# USB.net
KiCad netlist of a schematic drawn in Altium Designer
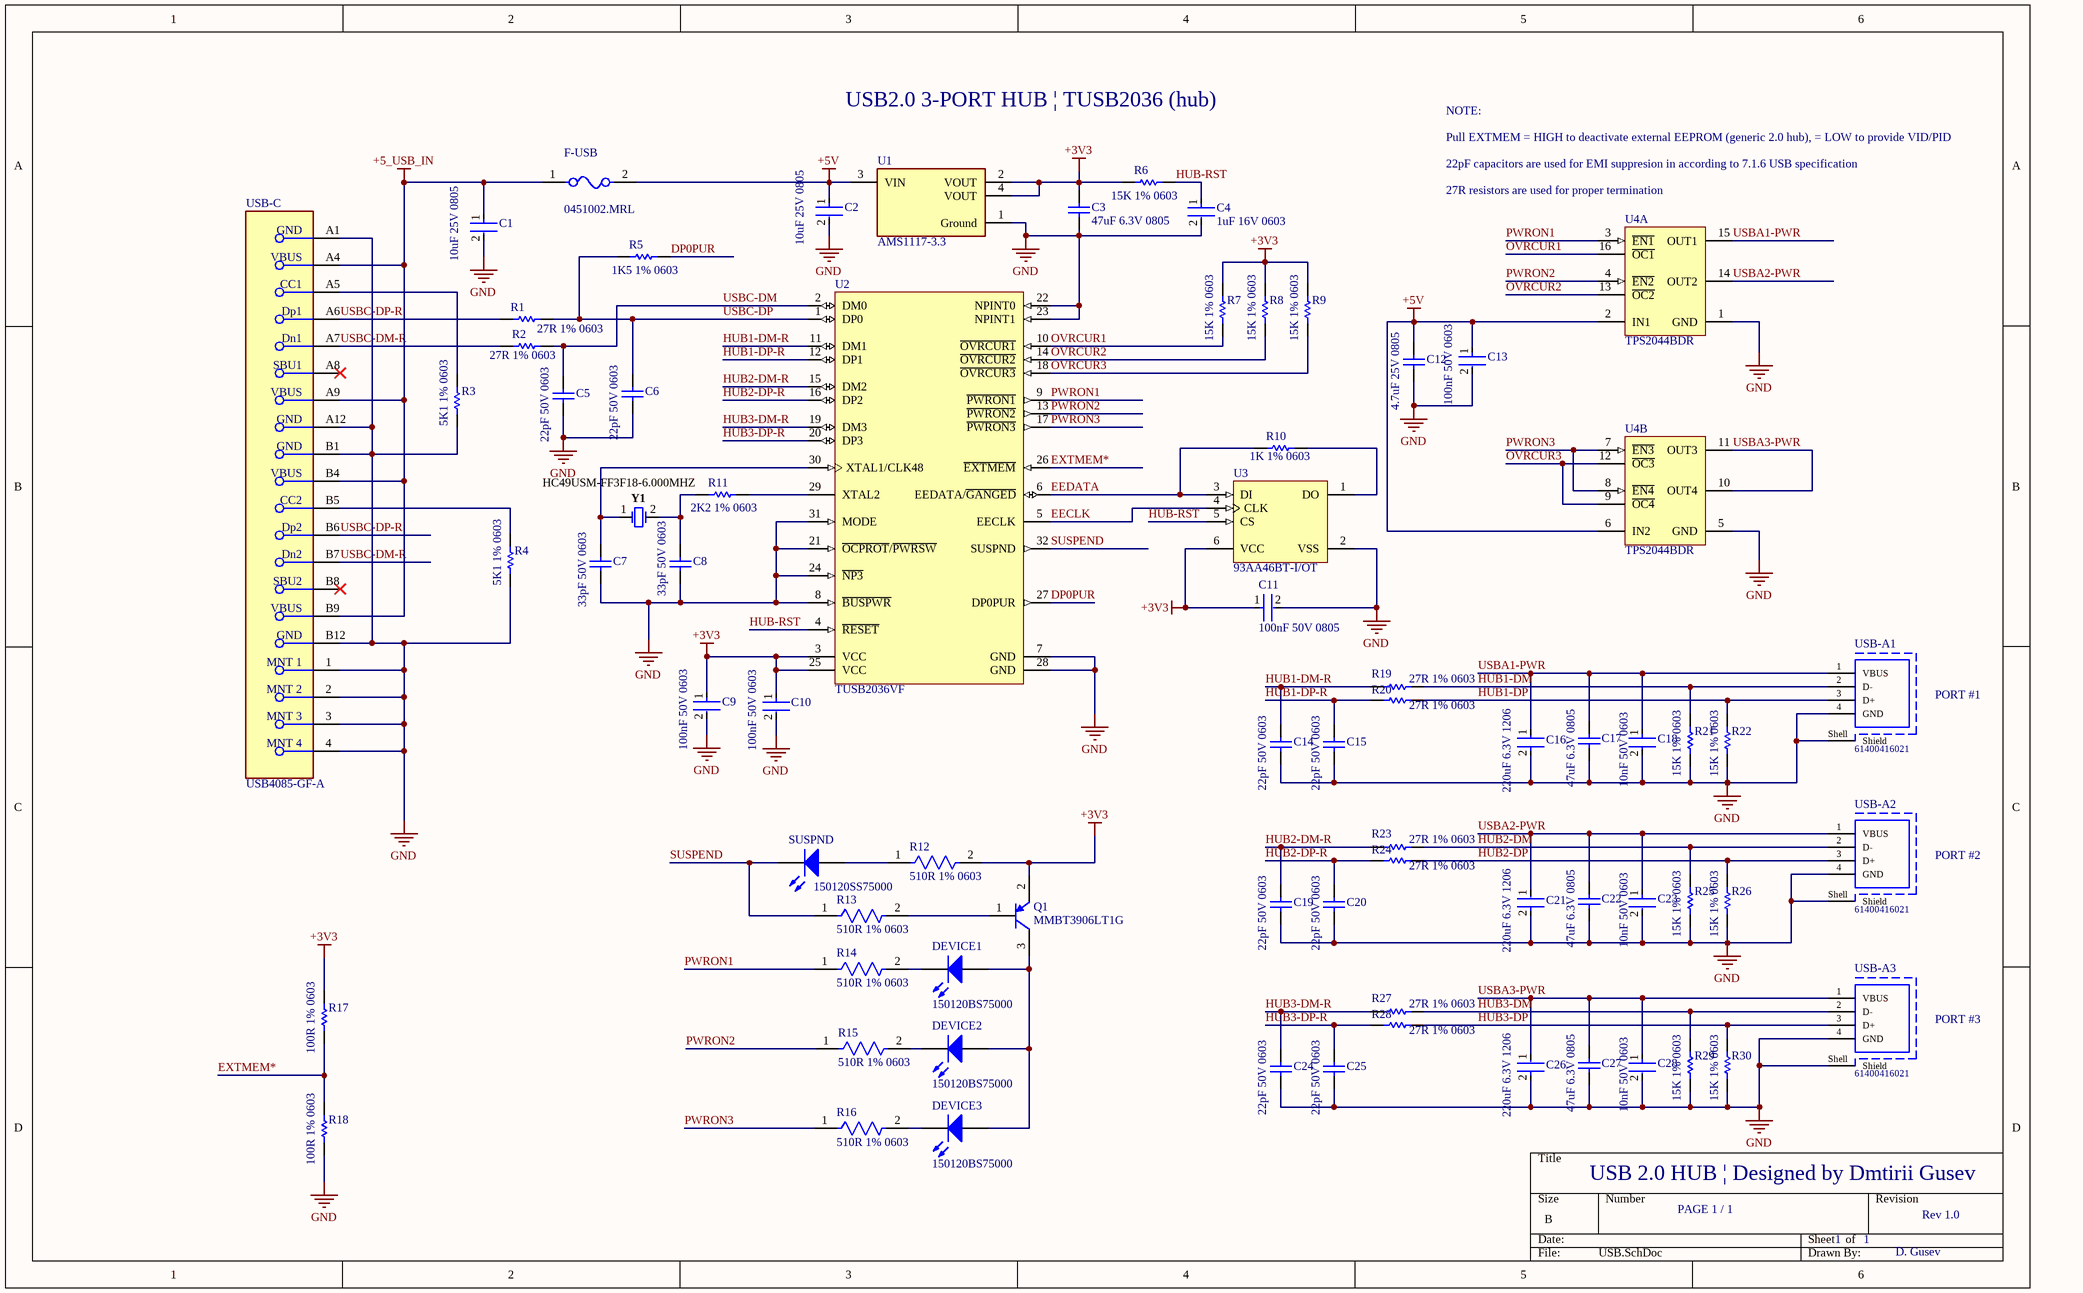
[diagram p0: USB.SchDoc]

(export (version "E")
  (design (tool "Eeschema 10.0.6"))
  (components
    (comp (ref "C1")
      (value "10uF 25V 0805")
      (footprint "FP-GRM21B-0_15-IPC_C")
      (description "Chip Multilayer Ceramic Capacitors for General Purpose, 0805, 10uF, X5R, 15%, 10%, 25V")
      (fields (field (name "VOLTAGE") "25V") (field (name "TOLERANCE") "10%"))
      (libsource (lib "Altium Content Vault") (part "b4654b650e69147ec39a6b967a45e02"))
    )
    (comp (ref "C2")
      (value "10uF 25V 0805")
      (footprint "FP-GRM21B-0_15-IPC_C")
      (description "Chip Multilayer Ceramic Capacitors for General Purpose, 0805, 10uF, X5R, 15%, 10%, 25V")
      (fields (field (name "VOLTAGE") "25V") (field (name "TOLERANCE") "10%"))
      (libsource (lib "Altium Content Vault") (part "b4654b650e69147ec39a6b967a45e02"))
    )
    (comp (ref "C3")
      (value "47uF 6.3V 0805")
      (footprint "CAPC2013X145X50LL20T25")
      (fields (field (name "MANUFACTURER") "Kemet") (field (name "PART NUMBER") "C0805C476M9PACTU"))
      (libsource (lib "Altium Content Vault") (part "CAP"))
    )
    (comp (ref "C4")
      (value "1uF 16V 0603")
      (footprint "FP-CC0603-DA-MFG")
      (description "CAP CER 1UF 16V X7R 0603")
      (fields (field (name "TOLERANCE") "0.1") (field (name "MANUFACTURER") "YAGEO"))
      (libsource (lib "Altium Content Vault") (part "11868f565c42a9108669ba33697ecf6"))
    )
    (comp (ref "C5")
      (value "22pF 50V 0603")
      (footprint "CAPC1608X90X35ML10T15")
      (description "Chip Capacitor, 22 pF, +/- 5%, 50 V, -55 to 125 degC, 0603 (1608 Metric), RoHS, Tape and Reel")
      (fields (field (name "MANUFACTURER") "Murata"))
      (libsource (lib "Altium Content Vault") (part "CAP-NP-2"))
    )
    (comp (ref "C6")
      (value "22pF 50V 0603")
      (footprint "CAPC1608X90X35ML10T15")
      (description "Chip Capacitor, 22 pF, +/- 5%, 50 V, -55 to 125 degC, 0603 (1608 Metric), RoHS, Tape and Reel")
      (fields (field (name "MANUFACTURER") "Murata"))
      (libsource (lib "Altium Content Vault") (part "CAP-NP-2"))
    )
    (comp (ref "C7")
      (value "33pF 50V 0603")
      (footprint "CAPC1608X90X40LL10T20")
      (description "Chip Capacitor, 33 pF, +/- 5%, 50 V, -55 to 125 degC, 0603 (1608 Metric), RoHS, Tape and Reel")
      (fields (field (name "MANUFACTURER") "Yageo") (field (name "TOLERANCE") "±5%"))
      (libsource (lib "Altium Content Vault") (part "CAP-NP-2"))
    )
    (comp (ref "C8")
      (value "33pF 50V 0603")
      (footprint "CAPC1608X90X40LL10T20")
      (description "Chip Capacitor, 33 pF, +/- 5%, 50 V, -55 to 125 degC, 0603 (1608 Metric), RoHS, Tape and Reel")
      (fields (field (name "MANUFACTURER") "Yageo") (field (name "TOLERANCE") "±5%"))
      (libsource (lib "Altium Content Vault") (part "CAP-NP-2"))
    )
    (comp (ref "C9")
      (value "100nF 50V 0603")
      (footprint "FP-CGA3E-0_3-0_1-IPC_A")
      (description "Cap Ceramic 100nF 50V X7R 10% Pad SMD 0603 +125°C Automotive T/R")
      (fields (field (name "TOLERANCE") "10%") (field (name "VOLTAGE") "50V"))
      (libsource (lib "Altium Content Vault") (part "b4654b650e69147ec39a6b967a45e02"))
    )
    (comp (ref "C10")
      (value "100nF 50V 0603")
      (footprint "FP-CGA3E-0_3-0_1-IPC_A")
      (description "Cap Ceramic 100nF 50V X7R 10% Pad SMD 0603 +125°C Automotive T/R")
      (fields (field (name "TOLERANCE") "10%") (field (name "VOLTAGE") "50V"))
      (libsource (lib "Altium Content Vault") (part "b4654b650e69147ec39a6b967a45e02"))
    )
    (comp (ref "C11")
      (value "100nF 50V 0805")
      (footprint "FP-C0805C-DN-MFG")
      (description "CAP CER 0.1UF 50V X7R 0805")
      (fields
        (field (name "MANUFACTURER PART NUMBER") "C0805C104K5RACTU")
        (field (name "MANUFACTURER") "KEMET")
      )
      (libsource (lib "Altium Content Vault") (part "b4654b650e69147ec39a6b967a45e02"))
    )
    (comp (ref "C12")
      (value "4.7uF 25V 0805")
      (footprint "CAPC2013X135X45ML10T25")
      (fields (field (name "MANUFACTURER") "Murata") (field (name "PART NUMBER") "GRM21BR61E475MA12L"))
      (libsource (lib "Altium Content Vault") (part "CAP"))
    )
    (comp (ref "C13")
      (value "100nF 50V 0603")
      (footprint "FP-CGA3E-0_3-0_1-IPC_A")
      (description "Cap Ceramic 100nF 50V X7R 10% Pad SMD 0603 +125°C Automotive T/R")
      (fields (field (name "TOLERANCE") "10%") (field (name "VOLTAGE") "50V"))
      (libsource (lib "Altium Content Vault") (part "b4654b650e69147ec39a6b967a45e02"))
    )
    (comp (ref "C14")
      (value "22pF 50V 0603")
      (footprint "CAPC1608X90X35ML10T15")
      (description "Chip Capacitor, 22 pF, +/- 5%, 50 V, -55 to 125 degC, 0603 (1608 Metric), RoHS, Tape and Reel")
      (fields (field (name "MANUFACTURER") "Murata"))
      (libsource (lib "Altium Content Vault") (part "CAP-NP-2"))
    )
    (comp (ref "C15")
      (value "22pF 50V 0603")
      (footprint "CAPC1608X90X35ML10T15")
      (description "Chip Capacitor, 22 pF, +/- 5%, 50 V, -55 to 125 degC, 0603 (1608 Metric), RoHS, Tape and Reel")
      (fields (field (name "MANUFACTURER") "Murata"))
      (libsource (lib "Altium Content Vault") (part "CAP-NP-2"))
    )
    (comp (ref "C16")
      (value "220uF 6.3V 1206")
      (footprint "FP-GRM31C-0_3-e0_3_0_9-IPC_C")
      (description "Chip Multilayer Ceramic Capacitors for General Purpose, 1206, 220uF, X5R, 15%, 20%, 6.3V")
      (fields (field (name "TOLERANCE") "20%"))
      (libsource (lib "Altium Content Vault") (part "f23184f103b6ebe33a8c269c53dcba6"))
    )
    (comp (ref "C17")
      (value "47uF 6.3V 0805")
      (footprint "CAPC2013X145X50LL20T25")
      (fields (field (name "MANUFACTURER") "Kemet") (field (name "PART NUMBER") "C0805C476M9PACTU"))
      (libsource (lib "Altium Content Vault") (part "CAP"))
    )
    (comp (ref "C18")
      (value "10nF 50V 0603")
      (footprint "FP-CC0603-DA-MFG")
      (description "CAP CER 10000PF 50V X7R 0603")
      (fields (field (name "TOLERANCE") "0.1") (field (name "MANUFACTURER PART NUMBER") "CC0603KRX7R9BB103"))
      (libsource (lib "Altium Content Vault") (part "11868f565c42a9108669ba33697ecf6"))
    )
    (comp (ref "C19")
      (value "22pF 50V 0603")
      (footprint "CAPC1608X90X35ML10T15")
      (description "Chip Capacitor, 22 pF, +/- 5%, 50 V, -55 to 125 degC, 0603 (1608 Metric), RoHS, Tape and Reel")
      (fields (field (name "MANUFACTURER") "Murata"))
      (libsource (lib "Altium Content Vault") (part "CAP-NP-2"))
    )
    (comp (ref "C20")
      (value "22pF 50V 0603")
      (footprint "CAPC1608X90X35ML10T15")
      (description "Chip Capacitor, 22 pF, +/- 5%, 50 V, -55 to 125 degC, 0603 (1608 Metric), RoHS, Tape and Reel")
      (fields (field (name "MANUFACTURER") "Murata"))
      (libsource (lib "Altium Content Vault") (part "CAP-NP-2"))
    )
    (comp (ref "C21")
      (value "220uF 6.3V 1206")
      (footprint "FP-GRM31C-0_3-e0_3_0_9-IPC_C")
      (description "Chip Multilayer Ceramic Capacitors for General Purpose, 1206, 220uF, X5R, 15%, 20%, 6.3V")
      (fields (field (name "TOLERANCE") "20%"))
      (libsource (lib "Altium Content Vault") (part "f23184f103b6ebe33a8c269c53dcba6"))
    )
    (comp (ref "C22")
      (value "47uF 6.3V 0805")
      (footprint "CAPC2013X145X50LL20T25")
      (fields (field (name "MANUFACTURER") "Kemet") (field (name "PART NUMBER") "C0805C476M9PACTU"))
      (libsource (lib "Altium Content Vault") (part "CAP"))
    )
    (comp (ref "C23")
      (value "10nF 50V 0603")
      (footprint "FP-CC0603-DA-MFG")
      (description "CAP CER 10000PF 50V X7R 0603")
      (fields (field (name "TOLERANCE") "0.1") (field (name "MANUFACTURER PART NUMBER") "CC0603KRX7R9BB103"))
      (libsource (lib "Altium Content Vault") (part "11868f565c42a9108669ba33697ecf6"))
    )
    (comp (ref "C24")
      (value "22pF 50V 0603")
      (footprint "CAPC1608X90X35ML10T15")
      (description "Chip Capacitor, 22 pF, +/- 5%, 50 V, -55 to 125 degC, 0603 (1608 Metric), RoHS, Tape and Reel")
      (fields (field (name "MANUFACTURER") "Murata"))
      (libsource (lib "Altium Content Vault") (part "CAP-NP-2"))
    )
    (comp (ref "C25")
      (value "22pF 50V 0603")
      (footprint "CAPC1608X90X35ML10T15")
      (description "Chip Capacitor, 22 pF, +/- 5%, 50 V, -55 to 125 degC, 0603 (1608 Metric), RoHS, Tape and Reel")
      (fields (field (name "MANUFACTURER") "Murata"))
      (libsource (lib "Altium Content Vault") (part "CAP-NP-2"))
    )
    (comp (ref "C26")
      (value "220uF 6.3V 1206")
      (footprint "FP-GRM31C-0_3-e0_3_0_9-IPC_C")
      (description "Chip Multilayer Ceramic Capacitors for General Purpose, 1206, 220uF, X5R, 15%, 20%, 6.3V")
      (fields (field (name "TOLERANCE") "20%"))
      (libsource (lib "Altium Content Vault") (part "f23184f103b6ebe33a8c269c53dcba6"))
    )
    (comp (ref "C27")
      (value "47uF 6.3V 0805")
      (footprint "CAPC2013X145X50LL20T25")
      (fields (field (name "MANUFACTURER") "Kemet") (field (name "PART NUMBER") "C0805C476M9PACTU"))
      (libsource (lib "Altium Content Vault") (part "CAP"))
    )
    (comp (ref "C28")
      (value "10nF 50V 0603")
      (footprint "FP-CC0603-DA-MFG")
      (description "CAP CER 10000PF 50V X7R 0603")
      (fields (field (name "TOLERANCE") "0.1") (field (name "MANUFACTURER PART NUMBER") "CC0603KRX7R9BB103"))
      (libsource (lib "Altium Content Vault") (part "11868f565c42a9108669ba33697ecf6"))
    )
    (comp (ref "DEVICE1")
      (value "150120BS75000")
      (footprint "1206_A")
      (description "SMD mono-color Chip LED, WL-SMCW, Blue")
      (fields (field (name "MANUFACTURER") "Wuerth Elektronik"))
      (libsource (lib "Altium Content Vault") (part "WE-LED_K1A2-2"))
    )
    (comp (ref "DEVICE2")
      (value "150120BS75000")
      (footprint "1206_A")
      (description "SMD mono-color Chip LED, WL-SMCW, Blue")
      (fields (field (name "MANUFACTURER") "Wuerth Elektronik"))
      (libsource (lib "Altium Content Vault") (part "WE-LED_K1A2-2"))
    )
    (comp (ref "DEVICE3")
      (value "150120BS75000")
      (footprint "1206_A")
      (description "SMD mono-color Chip LED, WL-SMCW, Blue")
      (fields (field (name "MANUFACTURER") "Wuerth Elektronik"))
      (libsource (lib "Altium Content Vault") (part "WE-LED_K1A2-2"))
    )
    (comp (ref "F-USB")
      (value "0451002.MRL")
      (footprint "FP-0451-MFG")
      (description "FUSE BOARD MNT 2A 125VAC/VDC SMD")
      (fields
        (field (name "MANUFACTURER") "Littelfuse")
        (field (name "OCTOPART") "https://octopart.com/0451002.mrl-littelfuse-566376")
      )
      (libsource (lib "Altium Content Vault") (part "5bcf9b9f640e542cf0359d10258e979"))
    )
    (comp (ref "Q1")
      (value "MMBT3906LT1G")
      (footprint "ONSC-SOT-23-3-318-08_V")
      (description "General Purpose Transistor, PNP Silicon, 3-Pin SOT-23, Pb-Free, Tape and Reel")
      (fields (field (name "MANUFACTURER") "On Semiconductor"))
      (libsource (lib "Altium Content Vault") (part "ONSC-PNP-B1E2C3-3"))
    )
    (comp (ref "R1")
      (value "27R 1% 0603")
      (footprint "RESC1608X55X30NL15T15")
      (fields (field (name "MANUFACTURER") "Panasonic") (field (name "PART NUMBER") "ERJ3EKF27R0V"))
      (libsource (lib "Altium Content Vault") (part "RES"))
    )
    (comp (ref "R2")
      (value "27R 1% 0603")
      (footprint "RESC1608X55X30NL15T15")
      (fields (field (name "MANUFACTURER") "Panasonic") (field (name "PART NUMBER") "ERJ3EKF27R0V"))
      (libsource (lib "Altium Content Vault") (part "RES"))
    )
    (comp (ref "R3")
      (value "5K1 1% 0603")
      (footprint "RESC1608X55X25ML10T15")
      (fields (field (name "MANUFACTURER") "Yageo") (field (name "PART NUMBER") "RC0603FR-075K1L"))
      (libsource (lib "Altium Content Vault") (part "RES"))
    )
    (comp (ref "R4")
      (value "5K1 1% 0603")
      (footprint "RESC1608X55X25ML10T15")
      (fields (field (name "MANUFACTURER") "Yageo") (field (name "PART NUMBER") "RC0603FR-075K1L"))
      (libsource (lib "Altium Content Vault") (part "RES"))
    )
    (comp (ref "R5")
      (value "1K5 1% 0603")
      (footprint "RESC1608X55X25ML10T15")
      (description "Chip Resistor, 1.5 KOhm, +/- 1%, 0.1 W, -55 to 155 degC, 0603 (1608 Metric), RoHS, Tape and Reel")
      (fields (field (name "TOLERANCE") "1%") (field (name "MANUFACTURER") "Yageo"))
      (libsource (lib "Altium Content Vault") (part "RES-2"))
    )
    (comp (ref "R6")
      (value "15K 1% 0603")
      (footprint "RESC1608X55X25ML10T15")
      (description "Chip Resistor, 15 KOhm, +/- 1%, 0.1 W, -55 to 155 degC, 0603 (1608 Metric), RoHS, Tape and Reel")
      (libsource (lib "Altium Content Vault") (part "RES-2"))
    )
    (comp (ref "R7")
      (value "15K 1% 0603")
      (footprint "RESC1608X55X25ML10T15")
      (description "Chip Resistor, 15 KOhm, +/- 1%, 0.1 W, -55 to 155 degC, 0603 (1608 Metric), RoHS, Tape and Reel")
      (libsource (lib "Altium Content Vault") (part "RES-2"))
    )
    (comp (ref "R8")
      (value "15K 1% 0603")
      (footprint "RESC1608X55X25ML10T15")
      (description "Chip Resistor, 15 KOhm, +/- 1%, 0.1 W, -55 to 155 degC, 0603 (1608 Metric), RoHS, Tape and Reel")
      (libsource (lib "Altium Content Vault") (part "RES-2"))
    )
    (comp (ref "R9")
      (value "15K 1% 0603")
      (footprint "RESC1608X55X25ML10T15")
      (description "Chip Resistor, 15 KOhm, +/- 1%, 0.1 W, -55 to 155 degC, 0603 (1608 Metric), RoHS, Tape and Reel")
      (libsource (lib "Altium Content Vault") (part "RES-2"))
    )
    (comp (ref "R10")
      (value "1K 1% 0603")
      (footprint "RESC1608X55X25NL10T15")
      (description "Chip Resistor, 1 KOhm, +/-1%, 0.1 W, -55 to 155 degC, 0603 (1608 Metric), RoHS, Tape and Reel")
      (fields (field (name "MANUFACTURER") "Yageo"))
      (libsource (lib "Altium Content Vault") (part "RES-2"))
    )
    (comp (ref "R11")
      (value "2K2 1% 0603")
      (footprint "RESC1608X55X25LL10T15")
      (fields (field (name "TOLERANCE") "1%") (field (name "MANUFACTURER") "Yageo"))
      (libsource (lib "Altium Content Vault") (part "RES-2"))
    )
    (comp (ref "R12")
      (value "510R 1% 0603")
      (footprint "FP-AC0603-MFG")
      (description "RES SMD 510 OHM 1% 1/10W 0603")
      (fields
        (field (name "MANUFACTURER") "Yageo")
        (field (name "OCTOPART") "https://octopart.com/ac0603fr-07510rl-yageo-33978667")
      )
      (libsource (lib "Altium Content Vault") (part "1029c3af85768c4190bb7ad29bc67b5"))
    )
    (comp (ref "R13")
      (value "510R 1% 0603")
      (footprint "FP-AC0603-MFG")
      (description "RES SMD 510 OHM 1% 1/10W 0603")
      (fields
        (field (name "MANUFACTURER") "Yageo")
        (field (name "OCTOPART") "https://octopart.com/ac0603fr-07510rl-yageo-33978667")
      )
      (libsource (lib "Altium Content Vault") (part "1029c3af85768c4190bb7ad29bc67b5"))
    )
    (comp (ref "R14")
      (value "510R 1% 0603")
      (footprint "FP-AC0603-MFG")
      (description "RES SMD 510 OHM 1% 1/10W 0603")
      (fields
        (field (name "MANUFACTURER") "Yageo")
        (field (name "OCTOPART") "https://octopart.com/ac0603fr-07510rl-yageo-33978667")
      )
      (libsource (lib "Altium Content Vault") (part "1029c3af85768c4190bb7ad29bc67b5"))
    )
    (comp (ref "R15")
      (value "510R 1% 0603")
      (footprint "FP-AC0603-MFG")
      (description "RES SMD 510 OHM 1% 1/10W 0603")
      (fields
        (field (name "MANUFACTURER") "Yageo")
        (field (name "OCTOPART") "https://octopart.com/ac0603fr-07510rl-yageo-33978667")
      )
      (libsource (lib "Altium Content Vault") (part "1029c3af85768c4190bb7ad29bc67b5"))
    )
    (comp (ref "R16")
      (value "510R 1% 0603")
      (footprint "FP-AC0603-MFG")
      (description "RES SMD 510 OHM 1% 1/10W 0603")
      (fields
        (field (name "MANUFACTURER") "Yageo")
        (field (name "OCTOPART") "https://octopart.com/ac0603fr-07510rl-yageo-33978667")
      )
      (libsource (lib "Altium Content Vault") (part "1029c3af85768c4190bb7ad29bc67b5"))
    )
    (comp (ref "R17")
      (value "100R 1% 0603")
      (footprint "RESC1608X55X25ML10T15")
      (description "Chip Resistor, 100 Ohm, +/- 1%, 0.1 W, -55 to 155 degC, 0603 (1608 Metric), RoHS, Tape and Reel")
      (fields (field (name "TOLERANCE") "1%") (field (name "MANUFACTURER") "Yageo"))
      (libsource (lib "Altium Content Vault") (part "RES-2"))
    )
    (comp (ref "R18")
      (value "100R 1% 0603")
      (footprint "RESC1608X55X25ML10T15")
      (description "Chip Resistor, 100 Ohm, +/- 1%, 0.1 W, -55 to 155 degC, 0603 (1608 Metric), RoHS, Tape and Reel")
      (fields (field (name "TOLERANCE") "1%") (field (name "MANUFACTURER") "Yageo"))
      (libsource (lib "Altium Content Vault") (part "RES-2"))
    )
    (comp (ref "R19")
      (value "27R 1% 0603")
      (footprint "RESC1608X55X30NL15T15")
      (fields (field (name "MANUFACTURER") "Panasonic") (field (name "PART NUMBER") "ERJ3EKF27R0V"))
      (libsource (lib "Altium Content Vault") (part "RES"))
    )
    (comp (ref "R20")
      (value "27R 1% 0603")
      (footprint "RESC1608X55X30NL15T15")
      (fields (field (name "MANUFACTURER") "Panasonic") (field (name "PART NUMBER") "ERJ3EKF27R0V"))
      (libsource (lib "Altium Content Vault") (part "RES"))
    )
    (comp (ref "R21")
      (value "15K 1% 0603")
      (footprint "RESC1608X55X25ML10T15")
      (description "Chip Resistor, 15 KOhm, +/- 1%, 0.1 W, -55 to 155 degC, 0603 (1608 Metric), RoHS, Tape and Reel")
      (libsource (lib "Altium Content Vault") (part "RES-2"))
    )
    (comp (ref "R22")
      (value "15K 1% 0603")
      (footprint "RESC1608X55X25ML10T15")
      (description "Chip Resistor, 15 KOhm, +/- 1%, 0.1 W, -55 to 155 degC, 0603 (1608 Metric), RoHS, Tape and Reel")
      (libsource (lib "Altium Content Vault") (part "RES-2"))
    )
    (comp (ref "R23")
      (value "27R 1% 0603")
      (footprint "RESC1608X55X30NL15T15")
      (fields (field (name "MANUFACTURER") "Panasonic") (field (name "PART NUMBER") "ERJ3EKF27R0V"))
      (libsource (lib "Altium Content Vault") (part "RES"))
    )
    (comp (ref "R24")
      (value "27R 1% 0603")
      (footprint "RESC1608X55X30NL15T15")
      (fields (field (name "MANUFACTURER") "Panasonic") (field (name "PART NUMBER") "ERJ3EKF27R0V"))
      (libsource (lib "Altium Content Vault") (part "RES"))
    )
    (comp (ref "R25")
      (value "15K 1% 0603")
      (footprint "RESC1608X55X25ML10T15")
      (description "Chip Resistor, 15 KOhm, +/- 1%, 0.1 W, -55 to 155 degC, 0603 (1608 Metric), RoHS, Tape and Reel")
      (libsource (lib "Altium Content Vault") (part "RES-2"))
    )
    (comp (ref "R26")
      (value "15K 1% 0603")
      (footprint "RESC1608X55X25ML10T15")
      (description "Chip Resistor, 15 KOhm, +/- 1%, 0.1 W, -55 to 155 degC, 0603 (1608 Metric), RoHS, Tape and Reel")
      (libsource (lib "Altium Content Vault") (part "RES-2"))
    )
    (comp (ref "R27")
      (value "27R 1% 0603")
      (footprint "RESC1608X55X30NL15T15")
      (fields (field (name "MANUFACTURER") "Panasonic") (field (name "PART NUMBER") "ERJ3EKF27R0V"))
      (libsource (lib "Altium Content Vault") (part "RES"))
    )
    (comp (ref "R28")
      (value "27R 1% 0603")
      (footprint "RESC1608X55X30NL15T15")
      (fields (field (name "MANUFACTURER") "Panasonic") (field (name "PART NUMBER") "ERJ3EKF27R0V"))
      (libsource (lib "Altium Content Vault") (part "RES"))
    )
    (comp (ref "R29")
      (value "15K 1% 0603")
      (footprint "RESC1608X55X25ML10T15")
      (description "Chip Resistor, 15 KOhm, +/- 1%, 0.1 W, -55 to 155 degC, 0603 (1608 Metric), RoHS, Tape and Reel")
      (libsource (lib "Altium Content Vault") (part "RES-2"))
    )
    (comp (ref "R30")
      (value "15K 1% 0603")
      (footprint "RESC1608X55X25ML10T15")
      (description "Chip Resistor, 15 KOhm, +/- 1%, 0.1 W, -55 to 155 degC, 0603 (1608 Metric), RoHS, Tape and Reel")
      (libsource (lib "Altium Content Vault") (part "RES-2"))
    )
    (comp (ref "SUSPND")
      (value "150120SS75000")
      (footprint "1206_A")
      (description "SMD mono-color Chip LED, WL-SMCW, Super Red")
      (fields (field (name "MANUFACTURER") "Wuerth Elektronik"))
      (libsource (lib "Altium Content Vault") (part "WE-LED_K1A2-2"))
    )
    (comp (ref "U1")
      (value "AMS1117-3.3")
      (footprint "FP-AMS1117-IPC_C")
      (description "LDO Voltage Regulators 1A, 3.3V")
      (fields
        (field (name "OCTOPART") "https://octopart.com/ams1117-3.3-advanced+monolithic+systems-25899300")
        (field (name "MANUFACTURER") "Advanced Monolithic Systems")
      )
      (libsource (lib "Altium Content Vault") (part "8bdbb5f8e77002000e30dd2845d0354"))
    )
    (comp (ref "U2")
      (value "TUSB2036VF")
      (footprint "VF0032A_N")
      (fields (field (name "MANUFACTURER") "Texas Instruments"))
      (libsource (lib "Altium Content Vault") (part "TI-TUSB2036-LQFP_VF-32"))
    )
    (comp (ref "U3")
      (value "93AA46BT-I/OT")
      (footprint "SOT-23-OT6_N")
      (description "1K, 64x16-bit, 1.8V Microwire Serial EEPROM, 6-Pin SOT-23, Industrial Temperature, Tape and Reel")
      (libsource (lib "Altium Content Vault") (part "MEM-SEEPROM-93AA46B-OT-6"))
    )
    (comp (ref "U4")
      (value "TPS2044BDR")
      (footprint "D0016A_M")
      (fields (field (name "MANUFACTURER") "Texas Instruments"))
      (libsource (lib "Altium Content Vault") (part "TI-TPS2044BD16"))
    )
    (comp (ref "USB-A1")
      (value "61400416021")
      (footprint "61400416021")
      (description "USB 2.0 Type A Receptacle WR-COM, Horizontal, THT")
      (fields (field (name "MANUFACTURER") "Wurth Elektronik") (field (name "PUBLISHER") "WurthElektronik"))
      (libsource (lib "Altium Content Vault") (part "WE-USB-4-1SHLD"))
    )
    (comp (ref "USB-A2")
      (value "61400416021")
      (footprint "61400416021")
      (description "USB 2.0 Type A Receptacle WR-COM, Horizontal, THT")
      (fields (field (name "MANUFACTURER") "Wurth Elektronik") (field (name "PUBLISHER") "WurthElektronik"))
      (libsource (lib "Altium Content Vault") (part "WE-USB-4-1SHLD"))
    )
    (comp (ref "USB-A3")
      (value "61400416021")
      (footprint "61400416021")
      (description "USB 2.0 Type A Receptacle WR-COM, Horizontal, THT")
      (fields (field (name "MANUFACTURER") "Wurth Elektronik") (field (name "PUBLISHER") "WurthElektronik"))
      (libsource (lib "Altium Content Vault") (part "WE-USB-4-1SHLD"))
    )
    (comp (ref "USB-C")
      (value "USB4085-GF-A")
      (footprint "FP-USB4085-GF-A-MFG")
      (description "CONN RCPT USB2.0 TYPEC 16POS")
      (fields
        (field (name "MANUFACTURER") "Global Connector Technology")
        (field (name "OCTOPART") "https://octopart.com/usb4085-gf-a-global+connector+technology-94773699")
      )
      (libsource (lib "Altium Content Vault") (part "f6997dba88850a18107ac0013977506"))
    )
    (comp (ref "Y1")
      (value "HC49USM-FF3F18-6.000MHZ")
      (footprint "ABRA-ABLS-14.7456MHZ-B2-T_V")
      (description "Low Profile Crystal, 14.7456 MHz, 18 pF, -20 to 70 degC, 2-Pin SMD, RoHS, Tape and Reel")
      (fields (field (name "MANUFACTURER") "ABRACON") (field (name "TOLERANCE") "20PPM"))
      (libsource (lib "Altium Content Vault") (part "XTAL-1-2-2"))
    )
  )
  (nets
    (net (code "1") (name "+3V3") (class "Default")
      (node (ref "C10") (pin "1") (pinfunction "1_1") (pintype "passive"))
      (node (ref "C11") (pin "1") (pinfunction "1_1") (pintype "passive"))
      (node (ref "C3") (pin "2") (pinfunction "2_2") (pintype "passive"))
      (node (ref "C9") (pin "1") (pinfunction "1_1") (pintype "passive"))
      (node (ref "Q1") (pin "2") (pinfunction "E_2") (pintype "passive"))
      (node (ref "R12") (pin "2") (pinfunction "2_2") (pintype "passive"))
      (node (ref "R17") (pin "2") (pinfunction "2_2") (pintype "passive"))
      (node (ref "R6") (pin "1") (pinfunction "1_1") (pintype "passive"))
      (node (ref "R7") (pin "2") (pinfunction "2_2") (pintype "passive"))
      (node (ref "R8") (pin "2") (pinfunction "2_2") (pintype "passive"))
      (node (ref "R9") (pin "2") (pinfunction "2_2") (pintype "passive"))
      (node (ref "U1") (pin "2") (pinfunction "VOUT_2") (pintype "passive"))
      (node (ref "U1") (pin "4") (pinfunction "VOUT_4") (pintype "passive"))
      (node (ref "U2") (pin "25") (pinfunction "VCC_25") (pintype "power_in"))
      (node (ref "U2") (pin "3") (pinfunction "VCC_3") (pintype "power_in"))
      (node (ref "U3") (pin "6") (pinfunction "VCC_6") (pintype "power_in"))
    )
    (net (code "2") (name "+5V") (class "Default")
      (node (ref "C12") (pin "2") (pinfunction "2_2") (pintype "passive"))
      (node (ref "C13") (pin "1") (pinfunction "1_1") (pintype "passive"))
      (node (ref "C2") (pin "1") (pinfunction "1_1") (pintype "passive"))
      (node (ref "F-USB") (pin "2") (pinfunction "2_2") (pintype "passive"))
      (node (ref "U1") (pin "3") (pinfunction "VIN_3") (pintype "power_in"))
      (node (ref "U4") (pin "2") (pinfunction "IN1_2") (pintype "power_in"))
      (node (ref "U4") (pin "6") (pinfunction "IN2_6") (pintype "power_in"))
    )
    (net (code "3") (name "+5_USB_IN") (class "Default")
      (node (ref "C1") (pin "1") (pinfunction "1_1") (pintype "passive"))
      (node (ref "F-USB") (pin "1") (pinfunction "1_1") (pintype "passive"))
      (node (ref "USB-C") (pin "A4") (pinfunction "VBUS_A4") (pintype "power_in"))
      (node (ref "USB-C") (pin "A9") (pinfunction "VBUS_A9") (pintype "power_in"))
      (node (ref "USB-C") (pin "B4") (pinfunction "VBUS_B4") (pintype "power_in"))
      (node (ref "USB-C") (pin "B9") (pinfunction "VBUS_B9") (pintype "power_in"))
    )
    (net (code "4") (name "/DP0PUR") (class "Default")
      (node (ref "R5") (pin "2") (pinfunction "2_2") (pintype "passive"))
      (node (ref "U2") (pin "27") (pinfunction "DP0PUR_27") (pintype "output"))
    )
    (net (code "5") (name "/EECLK") (class "Default")
      (node (ref "U2") (pin "5") (pinfunction "EECLK_5") (pintype "tri_state"))
      (node (ref "U3") (pin "4") (pinfunction "CLK_4") (pintype "input"))
    )
    (net (code "6") (name "/EEDATA") (class "Default")
      (node (ref "R10") (pin "1") (pinfunction "1_1") (pintype "passive"))
      (node (ref "U2") (pin "6") (pinfunction "EEDATA/~{GANGED}_6") (pintype "bidirectional"))
      (node (ref "U3") (pin "3") (pinfunction "DI_3") (pintype "input"))
    )
    (net (code "7") (name "/EXTMEM*") (class "Default")
      (node (ref "R17") (pin "1") (pinfunction "1_1") (pintype "passive"))
      (node (ref "R18") (pin "2") (pinfunction "2_2") (pintype "passive"))
      (node (ref "U2") (pin "26") (pinfunction "~{EXTMEM}_26") (pintype "input"))
    )
    (net (code "8") (name "/HUB-RST") (class "Default")
      (node (ref "C4") (pin "1") (pinfunction "1_1") (pintype "passive"))
      (node (ref "R6") (pin "2") (pinfunction "2_2") (pintype "passive"))
      (node (ref "U2") (pin "4") (pinfunction "~{RESET}_4") (pintype "input"))
      (node (ref "U3") (pin "5") (pinfunction "CS_5") (pintype "input"))
    )
    (net (code "9") (name "/HUB1-DM") (class "Default")
      (node (ref "R19") (pin "2") (pinfunction "2_2") (pintype "passive"))
      (node (ref "R21") (pin "2") (pinfunction "2_2") (pintype "passive"))
      (node (ref "USB-A1") (pin "2") (pinfunction "D-_2") (pintype "passive"))
    )
    (net (code "10") (name "/HUB1-DM-R") (class "Default")
      (node (ref "C14") (pin "2") (pinfunction "2_2") (pintype "passive"))
      (node (ref "R19") (pin "1") (pinfunction "1_1") (pintype "passive"))
      (node (ref "U2") (pin "11") (pinfunction "DM1_11") (pintype "bidirectional"))
    )
    (net (code "11") (name "/HUB1-DP") (class "Default")
      (node (ref "R20") (pin "2") (pinfunction "2_2") (pintype "passive"))
      (node (ref "R22") (pin "2") (pinfunction "2_2") (pintype "passive"))
      (node (ref "USB-A1") (pin "3") (pinfunction "D+_3") (pintype "passive"))
    )
    (net (code "12") (name "/HUB1-DP-R") (class "Default")
      (node (ref "C15") (pin "2") (pinfunction "2_2") (pintype "passive"))
      (node (ref "R20") (pin "1") (pinfunction "1_1") (pintype "passive"))
      (node (ref "U2") (pin "12") (pinfunction "DP1_12") (pintype "bidirectional"))
    )
    (net (code "13") (name "/HUB2-DM") (class "Default")
      (node (ref "R23") (pin "2") (pinfunction "2_2") (pintype "passive"))
      (node (ref "R25") (pin "2") (pinfunction "2_2") (pintype "passive"))
      (node (ref "USB-A2") (pin "2") (pinfunction "D-_2") (pintype "passive"))
    )
    (net (code "14") (name "/HUB2-DM-R") (class "Default")
      (node (ref "C19") (pin "2") (pinfunction "2_2") (pintype "passive"))
      (node (ref "R23") (pin "1") (pinfunction "1_1") (pintype "passive"))
      (node (ref "U2") (pin "15") (pinfunction "DM2_15") (pintype "bidirectional"))
    )
    (net (code "15") (name "/HUB2-DP") (class "Default")
      (node (ref "R24") (pin "2") (pinfunction "2_2") (pintype "passive"))
      (node (ref "R26") (pin "2") (pinfunction "2_2") (pintype "passive"))
      (node (ref "USB-A2") (pin "3") (pinfunction "D+_3") (pintype "passive"))
    )
    (net (code "16") (name "/HUB2-DP-R") (class "Default")
      (node (ref "C20") (pin "2") (pinfunction "2_2") (pintype "passive"))
      (node (ref "R24") (pin "1") (pinfunction "1_1") (pintype "passive"))
      (node (ref "U2") (pin "16") (pinfunction "DP2_16") (pintype "bidirectional"))
    )
    (net (code "17") (name "/HUB3-DM") (class "Default")
      (node (ref "R27") (pin "2") (pinfunction "2_2") (pintype "passive"))
      (node (ref "R29") (pin "2") (pinfunction "2_2") (pintype "passive"))
      (node (ref "USB-A3") (pin "2") (pinfunction "D-_2") (pintype "passive"))
    )
    (net (code "18") (name "/HUB3-DM-R") (class "Default")
      (node (ref "C24") (pin "2") (pinfunction "2_2") (pintype "passive"))
      (node (ref "R27") (pin "1") (pinfunction "1_1") (pintype "passive"))
      (node (ref "U2") (pin "19") (pinfunction "DM3_19") (pintype "bidirectional"))
    )
    (net (code "19") (name "/HUB3-DP") (class "Default")
      (node (ref "R28") (pin "2") (pinfunction "2_2") (pintype "passive"))
      (node (ref "R30") (pin "2") (pinfunction "2_2") (pintype "passive"))
      (node (ref "USB-A3") (pin "3") (pinfunction "D+_3") (pintype "passive"))
    )
    (net (code "20") (name "/HUB3-DP-R") (class "Default")
      (node (ref "C25") (pin "2") (pinfunction "2_2") (pintype "passive"))
      (node (ref "R28") (pin "1") (pinfunction "1_1") (pintype "passive"))
      (node (ref "U2") (pin "20") (pinfunction "DP3_20") (pintype "bidirectional"))
    )
    (net (code "21") (name "/OVRCUR1") (class "Default")
      (node (ref "R7") (pin "1") (pinfunction "1_1") (pintype "passive"))
      (node (ref "U2") (pin "10") (pinfunction "~{OVRCUR1}_10") (pintype "input"))
      (node (ref "U4") (pin "16") (pinfunction "~{OC1}_16") (pintype "open_collector"))
    )
    (net (code "22") (name "/OVRCUR2") (class "Default")
      (node (ref "R8") (pin "1") (pinfunction "1_1") (pintype "passive"))
      (node (ref "U2") (pin "14") (pinfunction "~{OVRCUR2}_14") (pintype "input"))
      (node (ref "U4") (pin "13") (pinfunction "~{OC2}_13") (pintype "open_collector"))
    )
    (net (code "23") (name "/OVRCUR3") (class "Default")
      (node (ref "R9") (pin "1") (pinfunction "1_1") (pintype "passive"))
      (node (ref "U2") (pin "18") (pinfunction "~{OVRCUR3}_18") (pintype "input"))
      (node (ref "U4") (pin "12") (pinfunction "~{OC3}_12") (pintype "open_collector"))
      (node (ref "U4") (pin "9") (pinfunction "~{OC4}_9") (pintype "open_collector"))
    )
    (net (code "24") (name "/PWRON1") (class "Default")
      (node (ref "R14") (pin "1") (pinfunction "1_1") (pintype "passive"))
      (node (ref "U2") (pin "9") (pinfunction "~{PWRON1}_9") (pintype "output"))
      (node (ref "U4") (pin "3") (pinfunction "~{EN1}_3") (pintype "input"))
    )
    (net (code "25") (name "/PWRON2") (class "Default")
      (node (ref "R15") (pin "1") (pinfunction "1_1") (pintype "passive"))
      (node (ref "U2") (pin "13") (pinfunction "~{PWRON2}_13") (pintype "output"))
      (node (ref "U4") (pin "4") (pinfunction "~{EN2}_4") (pintype "input"))
    )
    (net (code "26") (name "/PWRON3") (class "Default")
      (node (ref "R16") (pin "1") (pinfunction "1_1") (pintype "passive"))
      (node (ref "U2") (pin "17") (pinfunction "~{PWRON3}_17") (pintype "output"))
      (node (ref "U4") (pin "7") (pinfunction "~{EN3}_7") (pintype "input"))
      (node (ref "U4") (pin "8") (pinfunction "~{EN4}_8") (pintype "input"))
    )
    (net (code "27") (name "/SUSPEND") (class "Default")
      (node (ref "R13") (pin "1") (pinfunction "1_1") (pintype "passive"))
      (node (ref "SUSPND") (pin "1") (pinfunction "K_1") (pintype "passive"))
      (node (ref "U2") (pin "32") (pinfunction "SUSPND_32") (pintype "output"))
    )
    (net (code "28") (name "/USBA1-PWR") (class "Default")
      (node (ref "C16") (pin "1") (pinfunction "1_1") (pintype "passive"))
      (node (ref "C17") (pin "2") (pinfunction "2_2") (pintype "passive"))
      (node (ref "C18") (pin "1") (pinfunction "1_1") (pintype "passive"))
      (node (ref "U4") (pin "15") (pinfunction "OUT1_15") (pintype "power_in"))
      (node (ref "USB-A1") (pin "1") (pinfunction "VBUS_1") (pintype "passive"))
    )
    (net (code "29") (name "/USBA2-PWR") (class "Default")
      (node (ref "C21") (pin "1") (pinfunction "1_1") (pintype "passive"))
      (node (ref "C22") (pin "2") (pinfunction "2_2") (pintype "passive"))
      (node (ref "C23") (pin "1") (pinfunction "1_1") (pintype "passive"))
      (node (ref "U4") (pin "14") (pinfunction "OUT2_14") (pintype "power_in"))
      (node (ref "USB-A2") (pin "1") (pinfunction "VBUS_1") (pintype "passive"))
    )
    (net (code "30") (name "/USBA3-PWR") (class "Default")
      (node (ref "C26") (pin "1") (pinfunction "1_1") (pintype "passive"))
      (node (ref "C27") (pin "2") (pinfunction "2_2") (pintype "passive"))
      (node (ref "C28") (pin "1") (pinfunction "1_1") (pintype "passive"))
      (node (ref "U4") (pin "10") (pinfunction "OUT4_10") (pintype "power_in"))
      (node (ref "U4") (pin "11") (pinfunction "OUT3_11") (pintype "power_in"))
      (node (ref "USB-A3") (pin "1") (pinfunction "VBUS_1") (pintype "passive"))
    )
    (net (code "31") (name "/USBC-DM") (class "Default")
      (node (ref "C5") (pin "2") (pinfunction "2_2") (pintype "passive"))
      (node (ref "R2") (pin "2") (pinfunction "2_2") (pintype "passive"))
      (node (ref "U2") (pin "2") (pinfunction "DM0_2") (pintype "bidirectional"))
    )
    (net (code "32") (name "/USBC-DM-R") (class "Default")
      (node (ref "R2") (pin "1") (pinfunction "1_1") (pintype "passive"))
      (node (ref "USB-C") (pin "A7") (pinfunction "Dn1_A7") (pintype "passive"))
      (node (ref "USB-C") (pin "B7") (pinfunction "Dn2_B7") (pintype "passive"))
    )
    (net (code "33") (name "/USBC-DP") (class "Default")
      (node (ref "C6") (pin "2") (pinfunction "2_2") (pintype "passive"))
      (node (ref "R1") (pin "2") (pinfunction "2_2") (pintype "passive"))
      (node (ref "R5") (pin "1") (pinfunction "1_1") (pintype "passive"))
      (node (ref "U2") (pin "1") (pinfunction "DP0_1") (pintype "bidirectional"))
    )
    (net (code "34") (name "/USBC-DP-R") (class "Default")
      (node (ref "R1") (pin "1") (pinfunction "1_1") (pintype "passive"))
      (node (ref "USB-C") (pin "A6") (pinfunction "Dp1_A6") (pintype "passive"))
      (node (ref "USB-C") (pin "B6") (pinfunction "Dp2_B6") (pintype "passive"))
    )
    (net (code "35") (name "GND") (class "Default")
      (node (ref "C1") (pin "2") (pinfunction "2_2") (pintype "passive"))
      (node (ref "C10") (pin "2") (pinfunction "2_2") (pintype "passive"))
      (node (ref "C11") (pin "2") (pinfunction "2_2") (pintype "passive"))
      (node (ref "C12") (pin "1") (pinfunction "1_1") (pintype "passive"))
      (node (ref "C13") (pin "2") (pinfunction "2_2") (pintype "passive"))
      (node (ref "C14") (pin "1") (pinfunction "1_1") (pintype "passive"))
      (node (ref "C15") (pin "1") (pinfunction "1_1") (pintype "passive"))
      (node (ref "C16") (pin "2") (pinfunction "2_2") (pintype "passive"))
      (node (ref "C17") (pin "1") (pinfunction "1_1") (pintype "passive"))
      (node (ref "C18") (pin "2") (pinfunction "2_2") (pintype "passive"))
      (node (ref "C19") (pin "1") (pinfunction "1_1") (pintype "passive"))
      (node (ref "C2") (pin "2") (pinfunction "2_2") (pintype "passive"))
      (node (ref "C20") (pin "1") (pinfunction "1_1") (pintype "passive"))
      (node (ref "C21") (pin "2") (pinfunction "2_2") (pintype "passive"))
      (node (ref "C22") (pin "1") (pinfunction "1_1") (pintype "passive"))
      (node (ref "C23") (pin "2") (pinfunction "2_2") (pintype "passive"))
      (node (ref "C24") (pin "1") (pinfunction "1_1") (pintype "passive"))
      (node (ref "C25") (pin "1") (pinfunction "1_1") (pintype "passive"))
      (node (ref "C26") (pin "2") (pinfunction "2_2") (pintype "passive"))
      (node (ref "C27") (pin "1") (pinfunction "1_1") (pintype "passive"))
      (node (ref "C28") (pin "2") (pinfunction "2_2") (pintype "passive"))
      (node (ref "C3") (pin "1") (pinfunction "1_1") (pintype "passive"))
      (node (ref "C4") (pin "2") (pinfunction "2_2") (pintype "passive"))
      (node (ref "C5") (pin "1") (pinfunction "1_1") (pintype "passive"))
      (node (ref "C6") (pin "1") (pinfunction "1_1") (pintype "passive"))
      (node (ref "C7") (pin "1") (pinfunction "1_1") (pintype "passive"))
      (node (ref "C8") (pin "1") (pinfunction "1_1") (pintype "passive"))
      (node (ref "C9") (pin "2") (pinfunction "2_2") (pintype "passive"))
      (node (ref "R18") (pin "1") (pinfunction "1_1") (pintype "passive"))
      (node (ref "R21") (pin "1") (pinfunction "1_1") (pintype "passive"))
      (node (ref "R22") (pin "1") (pinfunction "1_1") (pintype "passive"))
      (node (ref "R25") (pin "1") (pinfunction "1_1") (pintype "passive"))
      (node (ref "R26") (pin "1") (pinfunction "1_1") (pintype "passive"))
      (node (ref "R29") (pin "1") (pinfunction "1_1") (pintype "passive"))
      (node (ref "R3") (pin "1") (pinfunction "1_1") (pintype "passive"))
      (node (ref "R30") (pin "1") (pinfunction "1_1") (pintype "passive"))
      (node (ref "R4") (pin "1") (pinfunction "1_1") (pintype "passive"))
      (node (ref "U1") (pin "1") (pinfunction "Ground_1") (pintype "power_in"))
      (node (ref "U2") (pin "21") (pinfunction "~{OCPROT}/~{PWRSW}_21") (pintype "input"))
      (node (ref "U2") (pin "22") (pinfunction "NPINT0_22") (pintype "input"))
      (node (ref "U2") (pin "23") (pinfunction "NPINT1_23") (pintype "input"))
      (node (ref "U2") (pin "24") (pinfunction "~{NP3}_24") (pintype "input"))
      (node (ref "U2") (pin "28") (pinfunction "GND_28") (pintype "power_in"))
      (node (ref "U2") (pin "31") (pinfunction "MODE_31") (pintype "input"))
      (node (ref "U2") (pin "7") (pinfunction "GND_7") (pintype "power_in"))
      (node (ref "U2") (pin "8") (pinfunction "~{BUSPWR}_8") (pintype "input"))
      (node (ref "U3") (pin "2") (pinfunction "VSS_2") (pintype "power_in"))
      (node (ref "U4") (pin "1") (pinfunction "GND_1") (pintype "power_in"))
      (node (ref "U4") (pin "5") (pinfunction "GND_5") (pintype "power_in"))
      (node (ref "USB-A1") (pin "4") (pinfunction "GND_4") (pintype "passive"))
      (node (ref "USB-A1") (pin "Shell") (pinfunction "Shield_Shell") (pintype "passive"))
      (node (ref "USB-A2") (pin "4") (pinfunction "GND_4") (pintype "passive"))
      (node (ref "USB-A2") (pin "Shell") (pinfunction "Shield_Shell") (pintype "passive"))
      (node (ref "USB-A3") (pin "4") (pinfunction "GND_4") (pintype "passive"))
      (node (ref "USB-A3") (pin "Shell") (pinfunction "Shield_Shell") (pintype "passive"))
      (node (ref "USB-C") (pin "1") (pinfunction "MNT_1_1") (pintype "passive"))
      (node (ref "USB-C") (pin "2") (pinfunction "MNT_2_2") (pintype "passive"))
      (node (ref "USB-C") (pin "3") (pinfunction "MNT_3_3") (pintype "passive"))
      (node (ref "USB-C") (pin "4") (pinfunction "MNT_4_4") (pintype "passive"))
      (node (ref "USB-C") (pin "A1") (pinfunction "GND_A1") (pintype "power_in"))
      (node (ref "USB-C") (pin "A12") (pinfunction "GND_A12") (pintype "power_in"))
      (node (ref "USB-C") (pin "B1") (pinfunction "GND_B1") (pintype "power_in"))
      (node (ref "USB-C") (pin "B12") (pinfunction "GND_B12") (pintype "power_in"))
    )
    (net (code "36") (name "Net-(C8-Pad2)") (class "Default")
      (node (ref "C8") (pin "2") (pinfunction "2_2") (pintype "passive"))
      (node (ref "R11") (pin "1") (pinfunction "1_1") (pintype "passive"))
      (node (ref "Y1") (pin "2") (pinfunction "2_2") (pintype "passive"))
    )
    (net (code "37") (name "Net-(DEVICE1-A)") (class "Default")
      (node (ref "DEVICE1") (pin "2") (pinfunction "A_2") (pintype "passive"))
      (node (ref "DEVICE2") (pin "2") (pinfunction "A_2") (pintype "passive"))
      (node (ref "DEVICE3") (pin "2") (pinfunction "A_2") (pintype "passive"))
      (node (ref "Q1") (pin "3") (pinfunction "C_3") (pintype "passive"))
    )
    (net (code "38") (name "Net-(DEVICE1-K)") (class "Default")
      (node (ref "DEVICE1") (pin "1") (pinfunction "K_1") (pintype "passive"))
      (node (ref "R14") (pin "2") (pinfunction "2_2") (pintype "passive"))
    )
    (net (code "39") (name "Net-(DEVICE2-K)") (class "Default")
      (node (ref "DEVICE2") (pin "1") (pinfunction "K_1") (pintype "passive"))
      (node (ref "R15") (pin "2") (pinfunction "2_2") (pintype "passive"))
    )
    (net (code "40") (name "Net-(DEVICE3-K)") (class "Default")
      (node (ref "DEVICE3") (pin "1") (pinfunction "K_1") (pintype "passive"))
      (node (ref "R16") (pin "2") (pinfunction "2_2") (pintype "passive"))
    )
    (net (code "41") (name "Net-(Q1-B)") (class "Default")
      (node (ref "Q1") (pin "1") (pinfunction "B_1") (pintype "passive"))
      (node (ref "R13") (pin "2") (pinfunction "2_2") (pintype "passive"))
    )
    (net (code "42") (name "Net-(SUSPND-A)") (class "Default")
      (node (ref "R12") (pin "1") (pinfunction "1_1") (pintype "passive"))
      (node (ref "SUSPND") (pin "2") (pinfunction "A_2") (pintype "passive"))
    )
    (net (code "43") (name "Net-(U2-XTAL1{slash}CLK48)") (class "Default")
      (node (ref "C7") (pin "2") (pinfunction "2_2") (pintype "passive"))
      (node (ref "U2") (pin "30") (pinfunction "XTAL1/CLK48_30") (pintype "input"))
      (node (ref "Y1") (pin "1") (pinfunction "1_1") (pintype "passive"))
    )
    (net (code "44") (name "Net-(U2-XTAL2)") (class "Default")
      (node (ref "R11") (pin "2") (pinfunction "2_2") (pintype "passive"))
      (node (ref "U2") (pin "29") (pinfunction "XTAL2_29") (pintype "passive"))
    )
    (net (code "45") (name "Net-(U3-DO)") (class "Default")
      (node (ref "R10") (pin "2") (pinfunction "2_2") (pintype "passive"))
      (node (ref "U3") (pin "1") (pinfunction "DO_1") (pintype "tri_state"))
    )
    (net (code "46") (name "Net-(USB-C-CC1)") (class "Default")
      (node (ref "R3") (pin "2") (pinfunction "2_2") (pintype "passive"))
      (node (ref "USB-C") (pin "A5") (pinfunction "CC1_A5") (pintype "passive"))
    )
    (net (code "47") (name "Net-(USB-C-CC2)") (class "Default")
      (node (ref "R4") (pin "2") (pinfunction "2_2") (pintype "passive"))
      (node (ref "USB-C") (pin "B5") (pinfunction "CC2_B5") (pintype "passive"))
    )
    (net (code "48") (name "unconnected-(USB-C-SBU1-PadA8)") (class "Default")
      (node (ref "USB-C") (pin "A8") (pinfunction "SBU1_A8") (pintype "passive+no_connect"))
    )
    (net (code "49") (name "unconnected-(USB-C-SBU2-PadB8)") (class "Default")
      (node (ref "USB-C") (pin "B8") (pinfunction "SBU2_B8") (pintype "passive+no_connect"))
    )
  )
)
